# design.net
KiCad netlist of a schematic drawn in Altium Designer
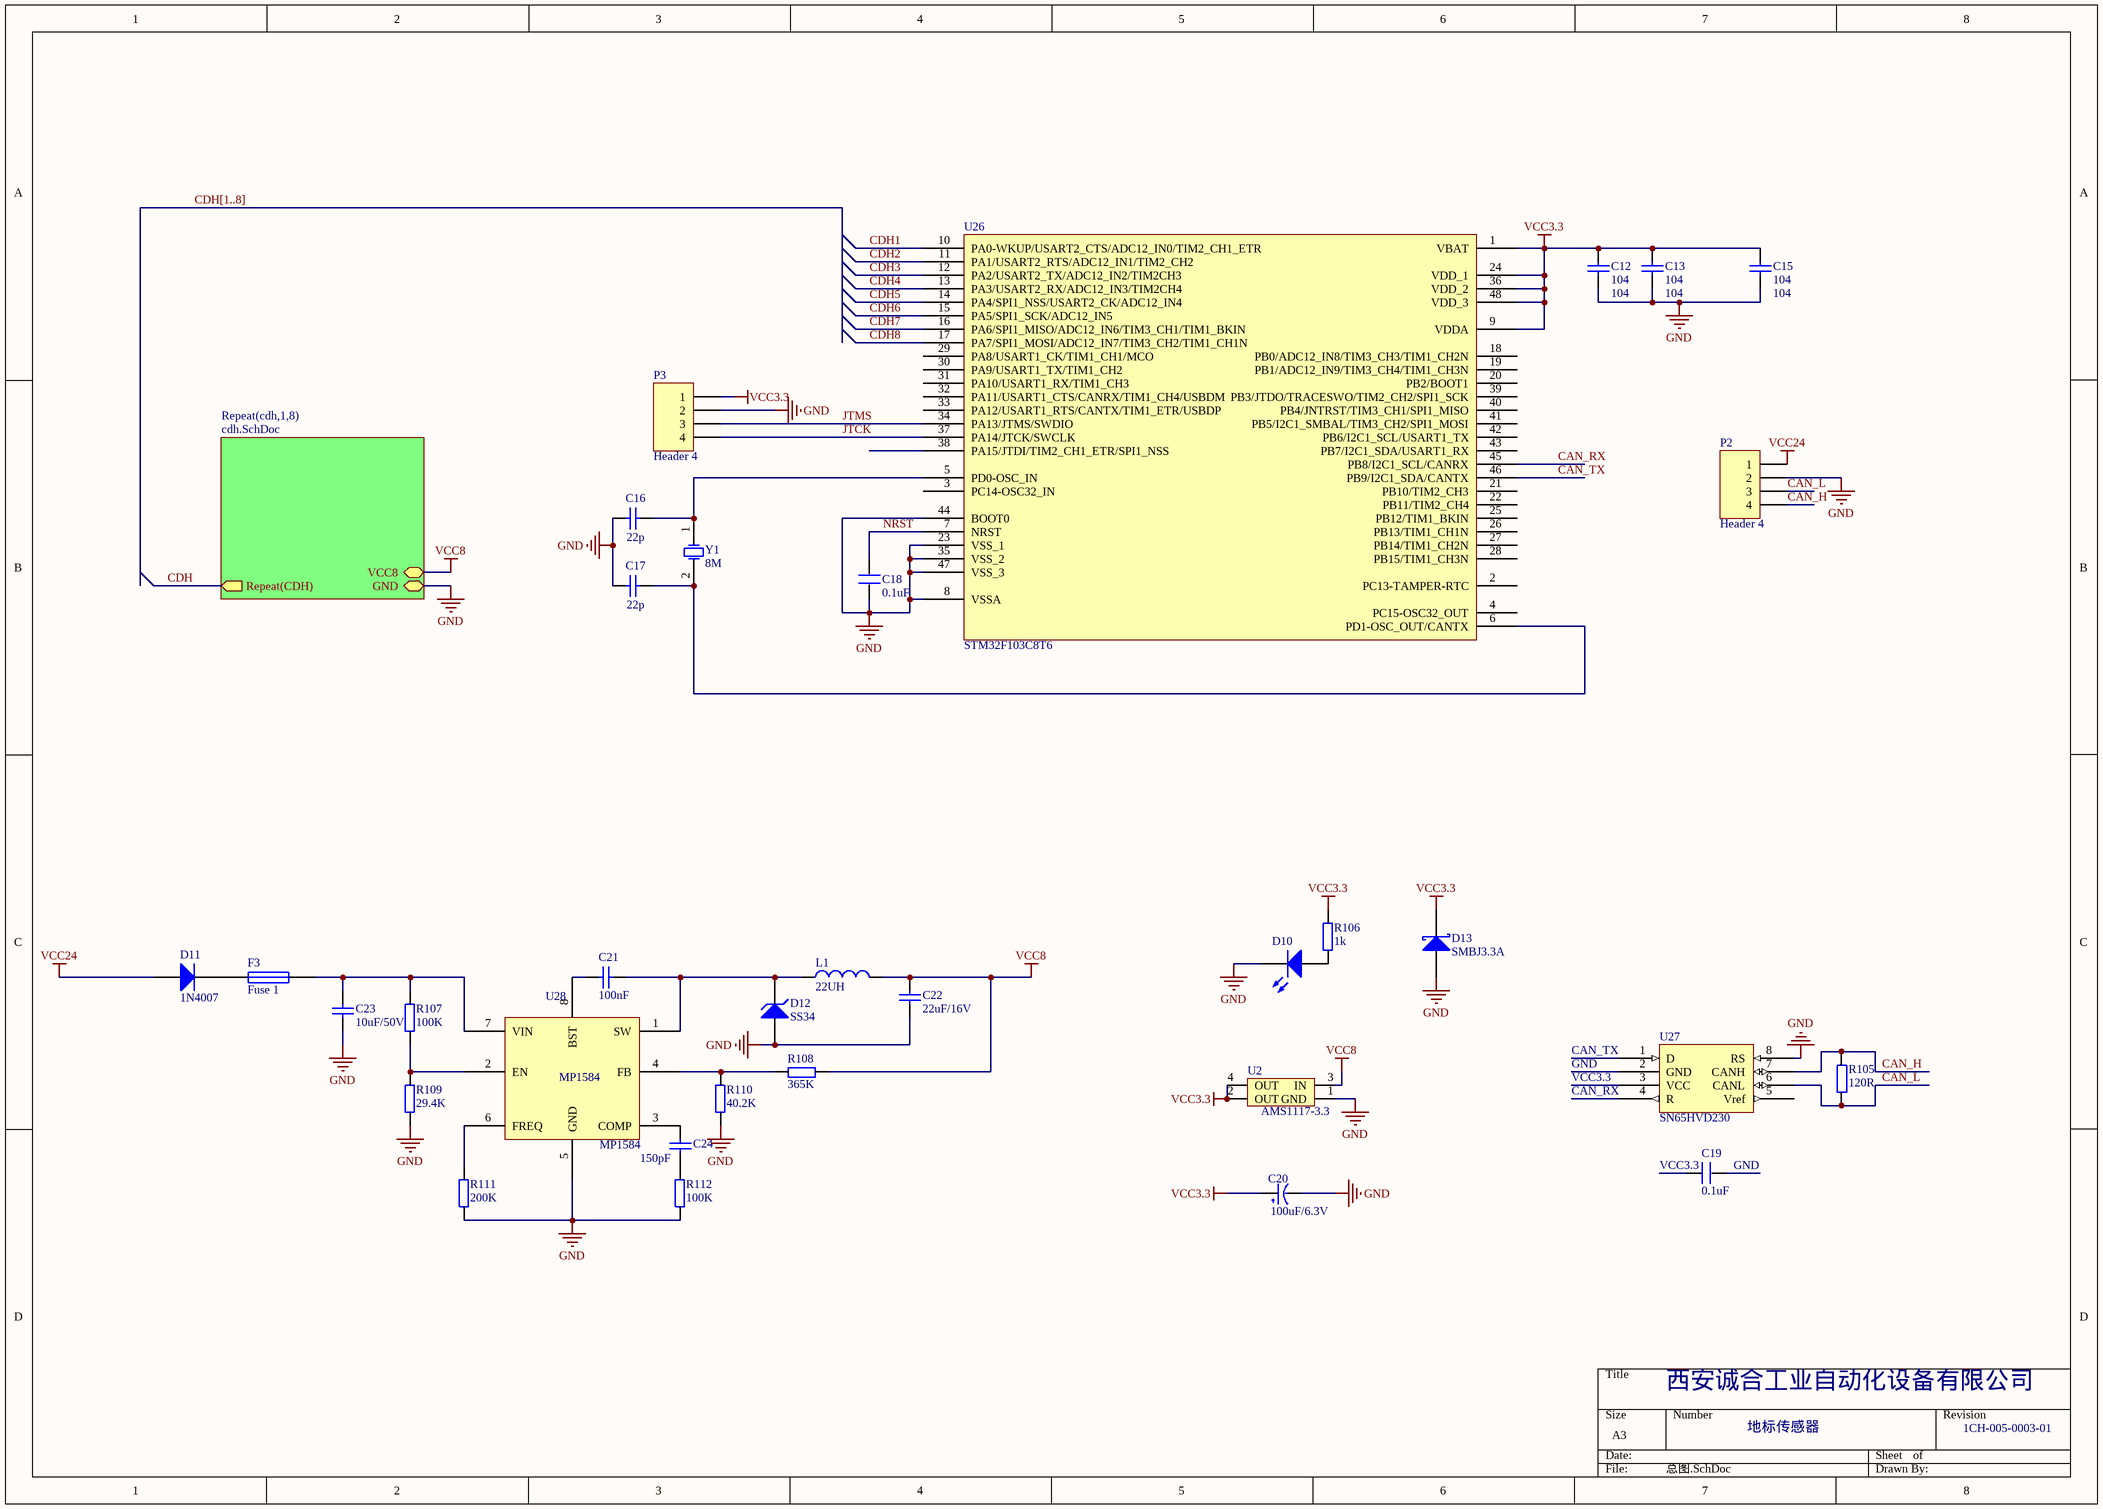
[diagram p0: 总图.SchDoc]

(export (version "E")
  (design (tool "Eeschema 10.0.6"))
  (components
    (comp (ref "C12")
      (value "104")
      (footprint "0603-CAP")
      (description "Capacitor")
      (fields (field (name "ALTIUM_VALUE") "104") (field (name "PUBLISHER") "Altium Limited"))
      (libsource (lib "Miscellaneous Devices") (part "Cap"))
    )
    (comp (ref "C13")
      (value "104")
      (footprint "0603-CAP")
      (description "Capacitor")
      (fields (field (name "ALTIUM_VALUE") "104") (field (name "PUBLISHER") "Altium Limited"))
      (libsource (lib "Miscellaneous Devices") (part "Cap"))
    )
    (comp (ref "C15")
      (value "104")
      (footprint "0603-CAP")
      (description "Capacitor")
      (fields (field (name "ALTIUM_VALUE") "104") (field (name "PUBLISHER") "Altium Limited"))
      (libsource (lib "Miscellaneous Devices") (part "Cap"))
    )
    (comp (ref "C16")
      (value "22p")
      (footprint "0603-CAP")
      (description "Capacitor")
      (fields (field (name "PUBLISHER") "Altium Limited"))
      (libsource (lib "Miscellaneous Devices") (part "Cap"))
    )
    (comp (ref "C17")
      (value "22p")
      (footprint "0603-CAP")
      (description "Capacitor")
      (fields (field (name "PUBLISHER") "Altium Limited"))
      (libsource (lib "Miscellaneous Devices") (part "Cap"))
    )
    (comp (ref "C18")
      (value "0.1uF")
      (footprint "0603-CAP")
      (libsource (lib "Explorer STM32F407封装库") (part "C"))
    )
    (comp (ref "C19")
      (value "0.1uF")
      (footprint "0603-CAP")
      (libsource (lib "Explorer STM32F407封装库") (part "C_3"))
    )
    (comp (ref "C20") (value "100uF/6.3V") (footprint "3216") (libsource (lib "WarShip V3_SCH") (part "CAP")))
    (comp (ref "C21")
      (value "100nF")
      (footprint "0603-CAP")
      (description "Capacitor (Semiconductor SIM Model)")
      (fields (field (name "Comment") "0.1uF") (field (name "PUBLISHER") "Altium Limited"))
      (libsource (lib "Miscellaneous Devices") (part "Cap Semi"))
    )
    (comp (ref "C22")
      (value "22uF/16V")
      (footprint "1206")
      (description "Capacitor (Semiconductor SIM Model)")
      (fields (field (name "PUBLISHER") "Altium Limited"))
      (libsource (lib "Miscellaneous Devices") (part "Cap Semi"))
    )
    (comp (ref "C23")
      (value "10uF/50V")
      (footprint "1206")
      (description "Capacitor (Semiconductor SIM Model)")
      (fields (field (name "PUBLISHER") "Altium Limited"))
      (libsource (lib "Miscellaneous Devices") (part "Cap Semi"))
    )
    (comp (ref "C24")
      (value "150pF")
      (footprint "0603-CAP")
      (description "Capacitor (Semiconductor SIM Model)")
      (fields (field (name "Comment") "0.1uF") (field (name "PUBLISHER") "Altium Limited"))
      (libsource (lib "Miscellaneous Devices") (part "Cap Semi"))
    )
    (comp (ref "D10")
      (value "LED0")
      (footprint "LC-0805_LED_S1")
      (description "Typical INFRARED GaAs LED")
      (fields (field (name "PUBLISHER") "Altium Limited"))
      (libsource (lib "继电器板_1") (part "LED0"))
    )
    (comp (ref "D11")
      (value "1N4007")
      (footprint "SMA(DO-214AC)_S1")
      (description "Default Diode")
      (fields (field (name "PUBLISHER") "Altium Limited"))
      (libsource (lib "Miscellaneous Devices") (part "Diode"))
    )
    (comp (ref "D12")
      (value "SS34")
      (footprint "SMA(DO-214AC)_S1")
      (description "Zener Diode")
      (fields (field (name "PUBLISHER") "Altium Limited"))
      (libsource (lib "Miscellaneous Devices") (part "D Zener"))
    )
    (comp (ref "D13")
      (value "SMBJ3.3A")
      (footprint "SMB(DO-214AA)_S1")
      (description "Schottky Rectifier")
      (fields (field (name "PUBLISHER") "Altium Limited"))
      (libsource (lib "Miscellaneous Devices") (part "Diode 18TQ045"))
    )
    (comp (ref "F3")
      (value "Fuse 1")
      (footprint "1206")
      (description "Fuse")
      (fields (field (name "PUBLISHER") "Altium Limited"))
      (libsource (lib "Miscellaneous Devices") (part "Fuse 1"))
    )
    (comp (ref "L1")
      (value "22UH")
      (footprint "L-7*7*4mm-S")
      (description "Inductor")
      (fields (field (name "PUBLISHER") "Altium Limited"))
      (libsource (lib "Miscellaneous Devices") (part "Inductor"))
    )
    (comp (ref "P2")
      (value "Header 4")
      (footprint "DZ-4-3.5")
      (description "Header, 4-Pin")
      (fields (field (name "PUBLISHER") "Altium Limited"))
      (libsource (lib "Miscellaneous Connectors") (part "Header 4"))
    )
    (comp (ref "P3")
      (value "Header 4")
      (footprint "HDR1X4")
      (description "Header, 4-Pin")
      (fields (field (name "PUBLISHER") "Altium Limited"))
      (libsource (lib "Miscellaneous Connectors") (part "Header 4"))
    )
    (comp (ref "R105")
      (value "120R")
      (footprint "0603")
      (libsource (lib "Explorer STM32F407封装库") (part "R_2"))
    )
    (comp (ref "R106") (value "1k") (footprint "0603") (libsource (lib "Explorer STM32F407封装库") (part "R_2")))
    (comp (ref "R107")
      (value "100K")
      (footprint "0603")
      (libsource (lib "Explorer STM32F407封装库") (part "R_2"))
    )
    (comp (ref "R108")
      (value "365K")
      (footprint "0603")
      (libsource (lib "Explorer STM32F407封装库") (part "R_2"))
    )
    (comp (ref "R109")
      (value "29.4K")
      (footprint "0603")
      (libsource (lib "Explorer STM32F407封装库") (part "R_2"))
    )
    (comp (ref "R110")
      (value "40.2K")
      (footprint "0603")
      (libsource (lib "Explorer STM32F407封装库") (part "R_2"))
    )
    (comp (ref "R111")
      (value "200K")
      (footprint "0603")
      (libsource (lib "Explorer STM32F407封装库") (part "R_2"))
    )
    (comp (ref "R112")
      (value "100K")
      (footprint "0603")
      (libsource (lib "Explorer STM32F407封装库") (part "R_2"))
    )
    (comp (ref "U2")
      (value "AMS1117-3.3")
      (footprint "LC-SOT-223")
      (libsource (lib "WarShip V3_SCH") (part "AMS1117"))
    )
    (comp (ref "U26")
      (value "STM32F103C8T6")
      (footprint "LC-LQFP-48")
      (libsource (lib "Schlib1") (part "stm32f103v8t6"))
    )
    (comp (ref "U27")
      (value "SN65HVD230")
      (footprint "SOP-8")
      (libsource (lib "Explorer STM32F407封装库") (part "SN65HVD230D"))
    )
    (comp (ref "U28") (value "MP1584") (footprint "SO-8") (libsource (lib "磁导航") (part "MP1584EN")))
    (comp (ref "Y1")
      (value "8M")
      (footprint "XTAL_US1")
      (description "Crystal Oscillator")
      (fields (field (name "PUBLISHER") "Altium Limited"))
      (libsource (lib "Miscellaneous Devices") (part "XTAL"))
    )
  )
  (nets
    (net (code "1") (name "/CAN_H") (class "Default")
      (node (ref "P2") (pin "4") (pinfunction "4_4") (pintype "passive"))
      (node (ref "R105") (pin "2") (pintype "passive"))
      (node (ref "U27") (pin "7") (pinfunction "CANH_7") (pintype "bidirectional"))
    )
    (net (code "2") (name "/CAN_L") (class "Default")
      (node (ref "P2") (pin "3") (pinfunction "3_3") (pintype "passive"))
      (node (ref "R105") (pin "1") (pintype "passive"))
      (node (ref "U27") (pin "6") (pinfunction "CANL_6") (pintype "bidirectional"))
    )
    (net (code "3") (name "/CAN_RX") (class "Default")
      (node (ref "U26") (pin "45") (pinfunction "PB8/I2C1_SCL/CANRX_45") (pintype "passive"))
      (node (ref "U27") (pin "4") (pinfunction "R_4") (pintype "output"))
    )
    (net (code "4") (name "/CAN_TX") (class "Default")
      (node (ref "U26") (pin "46") (pinfunction "PB9/I2C1_SDA/CANTX_46") (pintype "passive"))
      (node (ref "U27") (pin "1") (pinfunction "D_1") (pintype "input"))
    )
    (net (code "6") (name "/CDH1") (class "Default")
      (node (ref "U26") (pin "10") (pinfunction "PA0-WKUP/USART2_CTS/ADC12_IN0/TIM2_CH1_ETR_10") (pintype "passive"))
    )
    (net (code "7") (name "/CDH2") (class "Default")
      (node (ref "U26") (pin "11") (pinfunction "PA1/USART2_RTS/ADC12_IN1/TIM2_CH2_11") (pintype "passive"))
    )
    (net (code "8") (name "/CDH3") (class "Default")
      (node (ref "U26") (pin "12") (pinfunction "PA2/USART2_TX/ADC12_IN2/TIM2CH3_12") (pintype "passive"))
    )
    (net (code "9") (name "/CDH4") (class "Default")
      (node (ref "U26") (pin "13") (pinfunction "PA3/USART2_RX/ADC12_IN3/TIM2CH4_13") (pintype "passive"))
    )
    (net (code "10") (name "/CDH5") (class "Default")
      (node (ref "U26") (pin "14") (pinfunction "PA4/SPI1_NSS/USART2_CK/ADC12_IN4_14") (pintype "passive"))
    )
    (net (code "11") (name "/CDH6") (class "Default")
      (node (ref "U26") (pin "15") (pinfunction "PA5/SPI1_SCK/ADC12_IN5_15") (pintype "passive"))
    )
    (net (code "12") (name "/CDH7") (class "Default")
      (node (ref "U26") (pin "16") (pinfunction "PA6/SPI1_MISO/ADC12_IN6/TIM3_CH1/TIM1_BKIN_16") (pintype "passive"))
    )
    (net (code "13") (name "/CDH8") (class "Default")
      (node (ref "U26") (pin "17") (pinfunction "PA7/SPI1_MOSI/ADC12_IN7/TIM3_CH2/TIM1_CH1N_17") (pintype "passive"))
    )
    (net (code "15") (name "/JTCK") (class "Default")
      (node (ref "P3") (pin "4") (pinfunction "4_4") (pintype "passive"))
      (node (ref "U26") (pin "37") (pinfunction "PA14/JTCK/SWCLK_37") (pintype "passive"))
    )
    (net (code "16") (name "/JTMS") (class "Default")
      (node (ref "P3") (pin "3") (pinfunction "3_3") (pintype "passive"))
      (node (ref "U26") (pin "34") (pinfunction "PA13/JTMS/SWDIO_34") (pintype "passive"))
    )
    (net (code "17") (name "/NRST") (class "Default")
      (node (ref "C18") (pin "2") (pintype "passive"))
      (node (ref "U26") (pin "7") (pinfunction "NRST_7") (pintype "passive"))
    )
    (net (code "18") (name "GND") (class "Default")
      (node (ref "C12") (pin "2") (pinfunction "2_2") (pintype "passive"))
      (node (ref "C13") (pin "2") (pinfunction "2_2") (pintype "passive"))
      (node (ref "C15") (pin "2") (pinfunction "2_2") (pintype "passive"))
      (node (ref "C16") (pin "2") (pinfunction "2_2") (pintype "passive"))
      (node (ref "C17") (pin "2") (pinfunction "2_2") (pintype "passive"))
      (node (ref "C18") (pin "1") (pintype "passive"))
      (node (ref "C19") (pin "2") (pintype "passive"))
      (node (ref "C20") (pin "2") (pinfunction "GND_2") (pintype "passive"))
      (node (ref "C22") (pin "1") (pinfunction "1_1") (pintype "passive"))
      (node (ref "C23") (pin "2") (pinfunction "2_2") (pintype "passive"))
      (node (ref "D10") (pin "K") (pinfunction "K_K") (pintype "passive"))
      (node (ref "D12") (pin "1") (pinfunction "A_1") (pintype "passive"))
      (node (ref "D13") (pin "2") (pinfunction "A_2") (pintype "passive"))
      (node (ref "P2") (pin "2") (pinfunction "2_2") (pintype "passive"))
      (node (ref "P3") (pin "2") (pinfunction "2_2") (pintype "passive"))
      (node (ref "R109") (pin "2") (pintype "passive"))
      (node (ref "R110") (pin "2") (pintype "passive"))
      (node (ref "R111") (pin "2") (pintype "passive"))
      (node (ref "R112") (pin "2") (pintype "passive"))
      (node (ref "U2") (pin "1") (pinfunction "GND_1") (pintype "passive"))
      (node (ref "U26") (pin "23") (pinfunction "VSS_1_23") (pintype "passive"))
      (node (ref "U26") (pin "35") (pinfunction "VSS_2_35") (pintype "passive"))
      (node (ref "U26") (pin "44") (pinfunction "BOOT0_44") (pintype "passive"))
      (node (ref "U26") (pin "47") (pinfunction "VSS_3_47") (pintype "passive"))
      (node (ref "U26") (pin "8") (pinfunction "VSSA_8") (pintype "passive"))
      (node (ref "U27") (pin "2") (pinfunction "GND_2") (pintype "power_in"))
      (node (ref "U27") (pin "8") (pinfunction "RS_8") (pintype "input"))
      (node (ref "U28") (pin "5") (pinfunction "GND_5") (pintype "passive"))
    )
    (net (code "19") (name "Net-(C24-Pad1)") (class "Default")
      (node (ref "C24") (pin "1") (pinfunction "1_1") (pintype "passive"))
      (node (ref "R112") (pin "1") (pintype "passive"))
    )
    (net (code "20") (name "Net-(D10-PadA)") (class "Default")
      (node (ref "D10") (pin "A") (pinfunction "A_A") (pintype "passive"))
      (node (ref "R106") (pin "2") (pintype "passive"))
    )
    (net (code "21") (name "Net-(D11-K)") (class "Default")
      (node (ref "D11") (pin "2") (pinfunction "K_2") (pintype "passive"))
      (node (ref "F3") (pin "1") (pinfunction "1_1") (pintype "passive"))
    )
    (net (code "22") (name "Net-(D12-K)") (class "Default")
      (node (ref "C21") (pin "1") (pinfunction "1_1") (pintype "passive"))
      (node (ref "D12") (pin "2") (pinfunction "K_2") (pintype "passive"))
      (node (ref "L1") (pin "1") (pinfunction "1_1") (pintype "passive"))
      (node (ref "U28") (pin "1") (pinfunction "SW_1") (pintype "passive"))
    )
    (net (code "23") (name "Net-(U26-PD0-OSC_IN)") (class "Default")
      (node (ref "C16") (pin "1") (pinfunction "1_1") (pintype "passive"))
      (node (ref "U26") (pin "5") (pinfunction "PD0-OSC_IN_5") (pintype "passive"))
      (node (ref "Y1") (pin "1") (pinfunction "OSC1_1") (pintype "passive"))
    )
    (net (code "24") (name "Net-(U26-PD1-OSC_OUT{slash}CANTX)") (class "Default")
      (node (ref "C17") (pin "1") (pinfunction "1_1") (pintype "passive"))
      (node (ref "U26") (pin "6") (pinfunction "PD1-OSC_OUT/CANTX_6") (pintype "passive"))
      (node (ref "Y1") (pin "2") (pinfunction "OSC2_2") (pintype "passive"))
    )
    (net (code "25") (name "Net-(U28-BST)") (class "Default")
      (node (ref "C21") (pin "2") (pinfunction "2_2") (pintype "passive"))
      (node (ref "U28") (pin "8") (pinfunction "BST_8") (pintype "passive"))
    )
    (net (code "26") (name "Net-(U28-COMP)") (class "Default")
      (node (ref "C24") (pin "2") (pinfunction "2_2") (pintype "passive"))
      (node (ref "U28") (pin "3") (pinfunction "COMP_3") (pintype "passive"))
    )
    (net (code "27") (name "Net-(U28-EN)") (class "Default")
      (node (ref "R107") (pin "2") (pintype "passive"))
      (node (ref "R109") (pin "1") (pintype "passive"))
      (node (ref "U28") (pin "2") (pinfunction "EN_2") (pintype "passive"))
    )
    (net (code "28") (name "Net-(U28-FB)") (class "Default")
      (node (ref "R108") (pin "1") (pintype "passive"))
      (node (ref "R110") (pin "1") (pintype "passive"))
      (node (ref "U28") (pin "4") (pinfunction "FB_4") (pintype "passive"))
    )
    (net (code "29") (name "Net-(U28-FREQ)") (class "Default")
      (node (ref "R111") (pin "1") (pintype "passive"))
      (node (ref "U28") (pin "6") (pinfunction "FREQ_6") (pintype "passive"))
    )
    (net (code "30") (name "Net-(U28-VIN)") (class "Default")
      (node (ref "C23") (pin "1") (pinfunction "1_1") (pintype "passive"))
      (node (ref "F3") (pin "2") (pinfunction "2_2") (pintype "passive"))
      (node (ref "R107") (pin "1") (pintype "passive"))
      (node (ref "U28") (pin "7") (pinfunction "VIN_7") (pintype "passive"))
    )
    (net (code "31") (name "VCC3.3") (class "Default")
      (node (ref "C12") (pin "1") (pinfunction "1_1") (pintype "passive"))
      (node (ref "C13") (pin "1") (pinfunction "1_1") (pintype "passive"))
      (node (ref "C15") (pin "1") (pinfunction "1_1") (pintype "passive"))
      (node (ref "C19") (pin "1") (pintype "passive"))
      (node (ref "C20") (pin "1") (pinfunction "VCC_1") (pintype "passive"))
      (node (ref "D13") (pin "1") (pinfunction "K_1") (pintype "passive"))
      (node (ref "P3") (pin "1") (pinfunction "1_1") (pintype "passive"))
      (node (ref "R106") (pin "1") (pintype "passive"))
      (node (ref "U2") (pin "2") (pinfunction "OUT_2") (pintype "passive"))
      (node (ref "U2") (pin "4") (pinfunction "OUT_4") (pintype "passive"))
      (node (ref "U26") (pin "1") (pinfunction "VBAT_1") (pintype "passive"))
      (node (ref "U26") (pin "24") (pinfunction "VDD_1_24") (pintype "passive"))
      (node (ref "U26") (pin "36") (pinfunction "VDD_2_36") (pintype "passive"))
      (node (ref "U26") (pin "48") (pinfunction "VDD_3_48") (pintype "passive"))
      (node (ref "U26") (pin "9") (pinfunction "VDDA_9") (pintype "passive"))
      (node (ref "U27") (pin "3") (pinfunction "VCC_3") (pintype "power_in"))
    )
    (net (code "32") (name "VCC8") (class "Default")
      (node (ref "C22") (pin "2") (pinfunction "2_2") (pintype "passive"))
      (node (ref "L1") (pin "2") (pinfunction "2_2") (pintype "passive"))
      (node (ref "R108") (pin "2") (pintype "passive"))
      (node (ref "U2") (pin "3") (pinfunction "IN_3") (pintype "passive"))
    )
    (net (code "33") (name "VCC24") (class "Default")
      (node (ref "D11") (pin "1") (pinfunction "A_1") (pintype "passive"))
      (node (ref "P2") (pin "1") (pinfunction "1_1") (pintype "passive"))
    )
    (net (code "34") (name "unconnected-(U26-PA8{slash}USART1_CK{slash}TIM1_CH1{slash}MCO-Pad29)") (class "Default")
      (node (ref "U26") (pin "29") (pinfunction "PA8/USART1_CK/TIM1_CH1/MCO_29") (pintype "passive"))
    )
    (net (code "35") (name "unconnected-(U26-PA9{slash}USART1_TX{slash}TIM1_CH2-Pad30)") (class "Default")
      (node (ref "U26") (pin "30") (pinfunction "PA9/USART1_TX/TIM1_CH2_30") (pintype "passive"))
    )
    (net (code "36") (name "unconnected-(U26-PA10{slash}USART1_RX{slash}TIM1_CH3-Pad31)") (class "Default")
      (node (ref "U26") (pin "31") (pinfunction "PA10/USART1_RX/TIM1_CH3_31") (pintype "passive"))
    )
    (net (code "37") (name "unconnected-(U26-PA11{slash}USART1_CTS{slash}CANRX{slash}TIM1_CH4{slash}USBDM-Pad32)") (class "Default")
      (node (ref "U26") (pin "32") (pinfunction "PA11/USART1_CTS/CANRX/TIM1_CH4/USBDM_32") (pintype "passive"))
    )
    (net (code "38") (name "unconnected-(U26-PA12{slash}USART1_RTS{slash}CANTX{slash}TIM1_ETR{slash}USBDP-Pad33)") (class "Default")
      (node (ref "U26") (pin "33") (pinfunction "PA12/USART1_RTS/CANTX/TIM1_ETR/USBDP_33") (pintype "passive"))
    )
    (net (code "39") (name "unconnected-(U26-PA15{slash}JTDI{slash}TIM2_CH1_ETR{slash}SPI1_NSS-Pad38)") (class "Default")
      (node (ref "U26") (pin "38") (pinfunction "PA15/JTDI/TIM2_CH1_ETR/SPI1_NSS_38") (pintype "passive"))
    )
    (net (code "40") (name "unconnected-(U26-PB0{slash}ADC12_IN8{slash}TIM3_CH3{slash}TIM1_CH2N-Pad18)") (class "Default")
      (node (ref "U26") (pin "18") (pinfunction "PB0/ADC12_IN8/TIM3_CH3/TIM1_CH2N_18") (pintype "passive"))
    )
    (net (code "41") (name "unconnected-(U26-PB1{slash}ADC12_IN9{slash}TIM3_CH4{slash}TIM1_CH3N-Pad19)") (class "Default")
      (node (ref "U26") (pin "19") (pinfunction "PB1/ADC12_IN9/TIM3_CH4/TIM1_CH3N_19") (pintype "passive"))
    )
    (net (code "42") (name "unconnected-(U26-PB2{slash}BOOT1-Pad20)") (class "Default")
      (node (ref "U26") (pin "20") (pinfunction "PB2/BOOT1_20") (pintype "passive"))
    )
    (net (code "43") (name "unconnected-(U26-PB3{slash}JTDO{slash}TRACESWO{slash}TIM2_CH2{slash}SPI1_SCK-Pad39)") (class "Default")
      (node (ref "U26") (pin "39") (pinfunction "PB3/JTDO/TRACESWO/TIM2_CH2/SPI1_SCK_39") (pintype "passive"))
    )
    (net (code "44") (name "unconnected-(U26-PB4{slash}JNTRST{slash}TIM3_CH1{slash}SPI1_MISO-Pad40)") (class "Default")
      (node (ref "U26") (pin "40") (pinfunction "PB4/JNTRST/TIM3_CH1/SPI1_MISO_40") (pintype "passive"))
    )
    (net (code "45") (name "unconnected-(U26-PB5{slash}I2C1_SMBAL{slash}TIM3_CH2{slash}SPI1_MOSI-Pad41)") (class "Default")
      (node (ref "U26") (pin "41") (pinfunction "PB5/I2C1_SMBAL/TIM3_CH2/SPI1_MOSI_41") (pintype "passive"))
    )
    (net (code "46") (name "unconnected-(U26-PB6{slash}I2C1_SCL{slash}USART1_TX-Pad42)") (class "Default")
      (node (ref "U26") (pin "42") (pinfunction "PB6/I2C1_SCL/USART1_TX_42") (pintype "passive"))
    )
    (net (code "47") (name "unconnected-(U26-PB7{slash}I2C1_SDA{slash}USART1_RX-Pad43)") (class "Default")
      (node (ref "U26") (pin "43") (pinfunction "PB7/I2C1_SDA/USART1_RX_43") (pintype "passive"))
    )
    (net (code "48") (name "unconnected-(U26-PB10{slash}TIM2_CH3-Pad21)") (class "Default")
      (node (ref "U26") (pin "21") (pinfunction "PB10/TIM2_CH3_21") (pintype "passive"))
    )
    (net (code "49") (name "unconnected-(U26-PB11{slash}TIM2_CH4-Pad22)") (class "Default")
      (node (ref "U26") (pin "22") (pinfunction "PB11/TIM2_CH4_22") (pintype "passive"))
    )
    (net (code "50") (name "unconnected-(U26-PB12{slash}TIM1_BKIN-Pad25)") (class "Default")
      (node (ref "U26") (pin "25") (pinfunction "PB12/TIM1_BKIN_25") (pintype "passive"))
    )
    (net (code "51") (name "unconnected-(U26-PB13{slash}TIM1_CH1N-Pad26)") (class "Default")
      (node (ref "U26") (pin "26") (pinfunction "PB13/TIM1_CH1N_26") (pintype "passive"))
    )
    (net (code "52") (name "unconnected-(U26-PB14{slash}TIM1_CH2N-Pad27)") (class "Default")
      (node (ref "U26") (pin "27") (pinfunction "PB14/TIM1_CH2N_27") (pintype "passive"))
    )
    (net (code "53") (name "unconnected-(U26-PB15{slash}TIM1_CH3N-Pad28)") (class "Default")
      (node (ref "U26") (pin "28") (pinfunction "PB15/TIM1_CH3N_28") (pintype "passive"))
    )
    (net (code "54") (name "unconnected-(U26-PC13-TAMPER-RTC-Pad2)") (class "Default")
      (node (ref "U26") (pin "2") (pinfunction "PC13-TAMPER-RTC_2") (pintype "passive"))
    )
    (net (code "55") (name "unconnected-(U26-PC14-OSC32_IN-Pad3)") (class "Default")
      (node (ref "U26") (pin "3") (pinfunction "PC14-OSC32_IN_3") (pintype "passive"))
    )
    (net (code "56") (name "unconnected-(U26-PC15-OSC32_OUT-Pad4)") (class "Default")
      (node (ref "U26") (pin "4") (pinfunction "PC15-OSC32_OUT_4") (pintype "passive"))
    )
    (net (code "57") (name "unconnected-(U27-Vref-Pad5)") (class "Default")
      (node (ref "U27") (pin "5") (pinfunction "Vref_5") (pintype "output"))
    )
  )
)
